# AHRS.net
KiCad netlist of a schematic drawn in Altium Designer
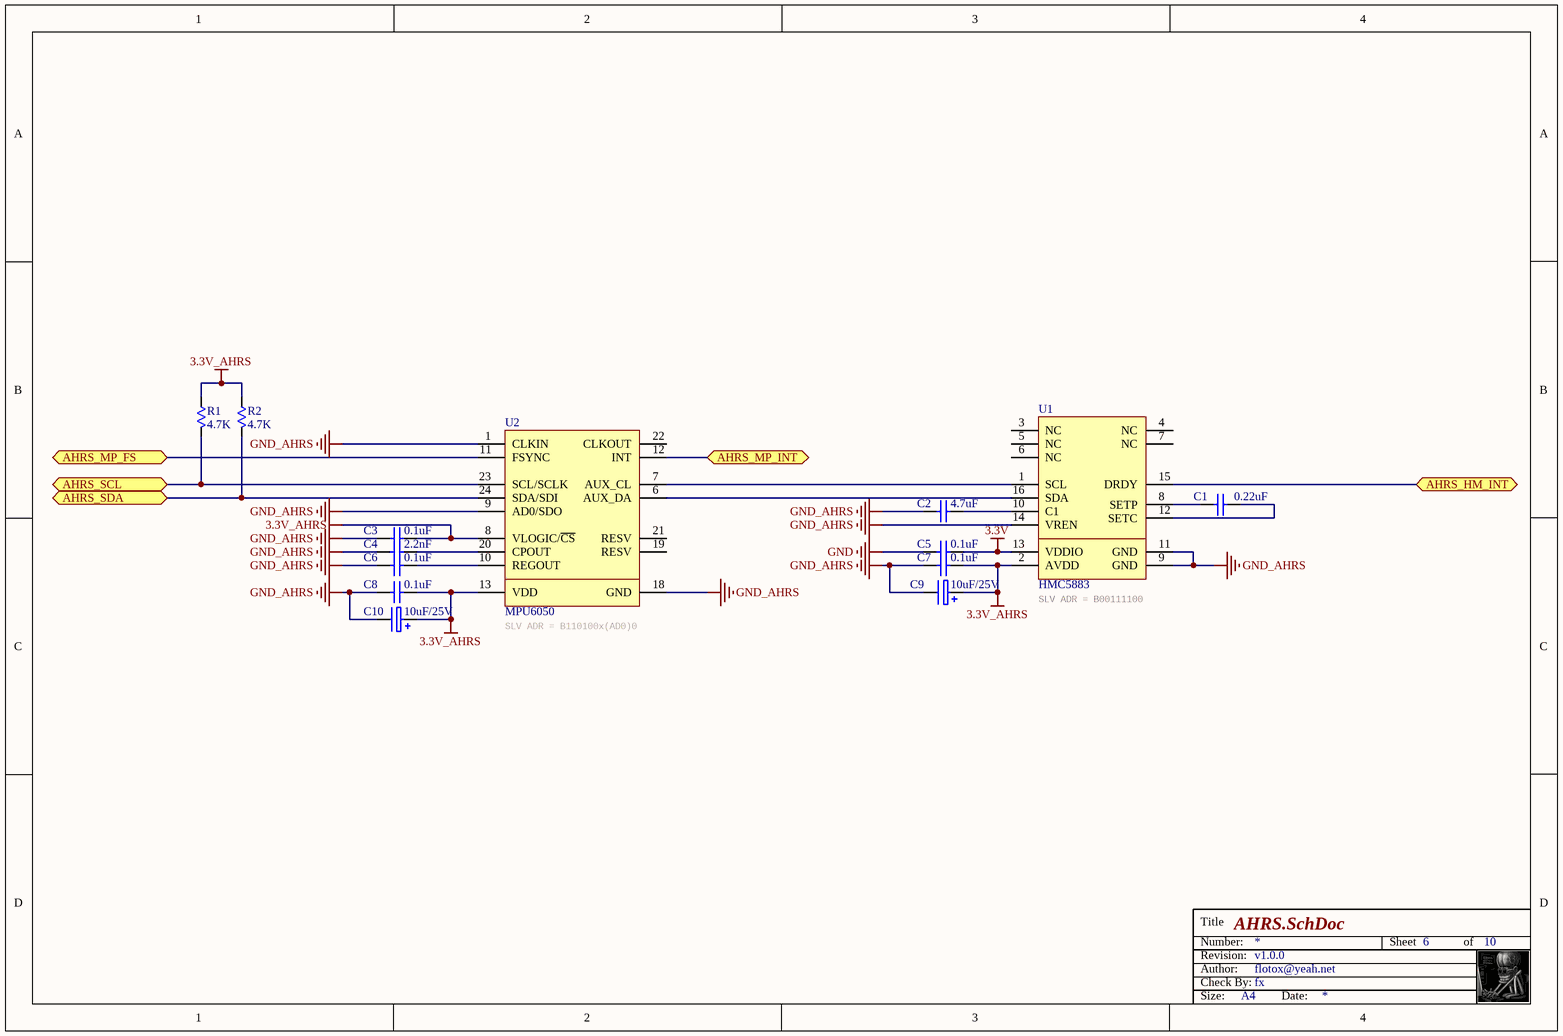
[diagram p0: AHRS.SchDoc]

(export (version "E")
  (design (tool "Eeschema 10.0.6"))
  (components
    (comp (ref "C1")
      (value "0.22uF")
      (footprint "C0603-S")
      (description "Capacitor")
      (libsource (lib "Passive Components Class") (part "CAP"))
    )
    (comp (ref "C2")
      (value "4.7uF")
      (footprint "C0603-S")
      (description "Capacitor")
      (libsource (lib "Passive Components Class") (part "CAP"))
    )
    (comp (ref "C3")
      (value "0.1uF")
      (footprint "C0603-S")
      (description "Capacitor")
      (libsource (lib "Passive Components Class") (part "CAP"))
    )
    (comp (ref "C4")
      (value "2.2nF")
      (footprint "C0603-S")
      (description "Capacitor")
      (libsource (lib "Passive Components Class") (part "CAP"))
    )
    (comp (ref "C5")
      (value "0.1uF")
      (footprint "C0603-S")
      (description "Capacitor")
      (libsource (lib "Passive Components Class") (part "CAP"))
    )
    (comp (ref "C6")
      (value "0.1uF")
      (footprint "C0603-S")
      (description "Capacitor")
      (libsource (lib "Passive Components Class") (part "CAP"))
    )
    (comp (ref "C7")
      (value "0.1uF")
      (footprint "C0603-S")
      (description "Capacitor")
      (libsource (lib "Passive Components Class") (part "CAP"))
    )
    (comp (ref "C8")
      (value "0.1uF")
      (footprint "C0603-S")
      (description "Capacitor")
      (libsource (lib "Passive Components Class") (part "CAP"))
    )
    (comp (ref "C9")
      (value "10uF/25V")
      (footprint "TC3528-1411")
      (description "Polarized Capacitor")
      (libsource (lib "Passive Components Class") (part "CAP-ELEC"))
    )
    (comp (ref "C10")
      (value "10uF/25V")
      (footprint "TC3528-1411")
      (description "Polarized Capacitor")
      (libsource (lib "Passive Components Class") (part "CAP-ELEC"))
    )
    (comp (ref "R1")
      (value "4.7K")
      (footprint "R0603-S")
      (description "Resistor")
      (libsource (lib "Passive Components Class") (part "RES"))
    )
    (comp (ref "R2")
      (value "4.7K")
      (footprint "R0603-S")
      (description "Resistor")
      (libsource (lib "Passive Components Class") (part "RES"))
    )
    (comp (ref "U1")
      (value "HMC5883")
      (footprint "QFN50P300X300-16")
      (description "3-Axis Digital Compass IC")
      (libsource (lib "Sensor Class") (part "HMC5883L"))
    )
    (comp (ref "U2")
      (value "MPU6050")
      (footprint "QFN50P400X400-24")
      (description "6-axis  MotionTracking  device")
      (libsource (lib "Sensor Class") (part "MPU60x0"))
    )
  )
  (nets
    (net (code "1") (name "/AHRS_HM_INT") (class "Default")
      (node (ref "U1") (pin "15") (pinfunction "DRDY_15") (pintype "passive"))
    )
    (net (code "2") (name "/AHRS_MP_FS") (class "Default")
      (node (ref "U2") (pin "11") (pinfunction "FSYNC_11") (pintype "passive"))
    )
    (net (code "3") (name "/AHRS_MP_INT") (class "Default")
      (node (ref "U2") (pin "12") (pinfunction "INT_12") (pintype "passive"))
    )
    (net (code "4") (name "/AHRS_SCL") (class "Default")
      (node (ref "R1") (pin "1") (pinfunction "1_1") (pintype "passive"))
      (node (ref "U2") (pin "23") (pinfunction "SCL/SCLK_23") (pintype "passive"))
    )
    (net (code "5") (name "/AHRS_SDA") (class "Default")
      (node (ref "R2") (pin "1") (pinfunction "1_1") (pintype "passive"))
      (node (ref "U2") (pin "24") (pinfunction "SDA/SDI_24") (pintype "passive"))
    )
    (net (code "6") (name "3.3V") (class "Default")
      (node (ref "C5") (pin "1") (pinfunction "1_1") (pintype "passive"))
      (node (ref "U1") (pin "13") (pinfunction "VDDIO_13") (pintype "passive"))
    )
    (net (code "7") (name "3.3V_AHRS") (class "Default")
      (node (ref "C10") (pin "1") (pinfunction "1_1") (pintype "passive"))
      (node (ref "C3") (pin "1") (pinfunction "1_1") (pintype "passive"))
      (node (ref "C7") (pin "1") (pinfunction "1_1") (pintype "passive"))
      (node (ref "C8") (pin "2") (pinfunction "2_2") (pintype "passive"))
      (node (ref "C9") (pin "1") (pinfunction "1_1") (pintype "passive"))
      (node (ref "R1") (pin "2") (pinfunction "2_2") (pintype "passive"))
      (node (ref "R2") (pin "2") (pinfunction "2_2") (pintype "passive"))
      (node (ref "U1") (pin "2") (pinfunction "AVDD_2") (pintype "passive"))
      (node (ref "U2") (pin "13") (pinfunction "VDD_13") (pintype "passive"))
      (node (ref "U2") (pin "8") (pinfunction "VLOGIC/~{CS}_8") (pintype "passive"))
    )
    (net (code "8") (name "GND") (class "Default")
      (node (ref "C5") (pin "2") (pinfunction "2_2") (pintype "passive"))
    )
    (net (code "9") (name "GND_AHRS") (class "Default")
      (node (ref "C10") (pin "2") (pinfunction "2_2") (pintype "passive"))
      (node (ref "C2") (pin "2") (pinfunction "2_2") (pintype "passive"))
      (node (ref "C3") (pin "2") (pinfunction "2_2") (pintype "passive"))
      (node (ref "C4") (pin "2") (pinfunction "2_2") (pintype "passive"))
      (node (ref "C6") (pin "1") (pinfunction "1_1") (pintype "passive"))
      (node (ref "C7") (pin "2") (pinfunction "2_2") (pintype "passive"))
      (node (ref "C8") (pin "1") (pinfunction "1_1") (pintype "passive"))
      (node (ref "C9") (pin "2") (pinfunction "2_2") (pintype "passive"))
      (node (ref "U1") (pin "11") (pinfunction "GND_11") (pintype "passive"))
      (node (ref "U1") (pin "14") (pinfunction "VREN_14") (pintype "passive"))
      (node (ref "U1") (pin "9") (pinfunction "GND_9") (pintype "passive"))
      (node (ref "U2") (pin "1") (pinfunction "CLKIN_1") (pintype "passive"))
      (node (ref "U2") (pin "18") (pinfunction "GND_18") (pintype "passive"))
      (node (ref "U2") (pin "9") (pinfunction "AD0/SDO_9") (pintype "passive"))
    )
    (net (code "10") (name "Net-(U1-C1)") (class "Default")
      (node (ref "C2") (pin "1") (pinfunction "1_1") (pintype "passive"))
      (node (ref "U1") (pin "10") (pinfunction "C1_10") (pintype "passive"))
    )
    (net (code "11") (name "Net-(U1-SCL)") (class "Default")
      (node (ref "U1") (pin "1") (pinfunction "SCL_1") (pintype "passive"))
      (node (ref "U2") (pin "7") (pinfunction "AUX_CL_7") (pintype "passive"))
    )
    (net (code "12") (name "Net-(U1-SDA)") (class "Default")
      (node (ref "U1") (pin "16") (pinfunction "SDA_16") (pintype "passive"))
      (node (ref "U2") (pin "6") (pinfunction "AUX_DA_6") (pintype "passive"))
    )
    (net (code "13") (name "Net-(U1-SETC)") (class "Default")
      (node (ref "C1") (pin "1") (pinfunction "1_1") (pintype "passive"))
      (node (ref "U1") (pin "12") (pinfunction "SETC_12") (pintype "passive"))
    )
    (net (code "14") (name "Net-(U1-SETP)") (class "Default")
      (node (ref "C1") (pin "2") (pinfunction "2_2") (pintype "passive"))
      (node (ref "U1") (pin "8") (pinfunction "SETP_8") (pintype "passive"))
    )
    (net (code "15") (name "Net-(U2-CPOUT)") (class "Default")
      (node (ref "C4") (pin "1") (pinfunction "1_1") (pintype "passive"))
      (node (ref "U2") (pin "20") (pinfunction "CPOUT_20") (pintype "passive"))
    )
    (net (code "16") (name "Net-(U2-REGOUT)") (class "Default")
      (node (ref "C6") (pin "2") (pinfunction "2_2") (pintype "passive"))
      (node (ref "U2") (pin "10") (pinfunction "REGOUT_10") (pintype "passive"))
    )
    (net (code "17") (name "unconnected-(U1-NC-Pad3)") (class "Default")
      (node (ref "U1") (pin "3") (pinfunction "NC_3") (pintype "passive"))
    )
    (net (code "18") (name "unconnected-(U1-NC-Pad4)") (class "Default")
      (node (ref "U1") (pin "4") (pinfunction "NC_4") (pintype "passive"))
    )
    (net (code "19") (name "unconnected-(U1-NC-Pad5)") (class "Default")
      (node (ref "U1") (pin "5") (pinfunction "NC_5") (pintype "passive"))
    )
    (net (code "20") (name "unconnected-(U1-NC-Pad6)") (class "Default")
      (node (ref "U1") (pin "6") (pinfunction "NC_6") (pintype "passive"))
    )
    (net (code "21") (name "unconnected-(U1-NC-Pad7)") (class "Default")
      (node (ref "U1") (pin "7") (pinfunction "NC_7") (pintype "passive"))
    )
    (net (code "22") (name "unconnected-(U2-CLKOUT-Pad22)") (class "Default")
      (node (ref "U2") (pin "22") (pinfunction "CLKOUT_22") (pintype "passive"))
    )
    (net (code "23") (name "unconnected-(U2-RESV-Pad19)") (class "Default")
      (node (ref "U2") (pin "19") (pinfunction "RESV_19") (pintype "passive"))
    )
    (net (code "24") (name "unconnected-(U2-RESV-Pad21)") (class "Default")
      (node (ref "U2") (pin "21") (pinfunction "RESV_21") (pintype "passive"))
    )
  )
)
